# HomeAutoModule.net
KiCad netlist of a schematic drawn in EAGLE
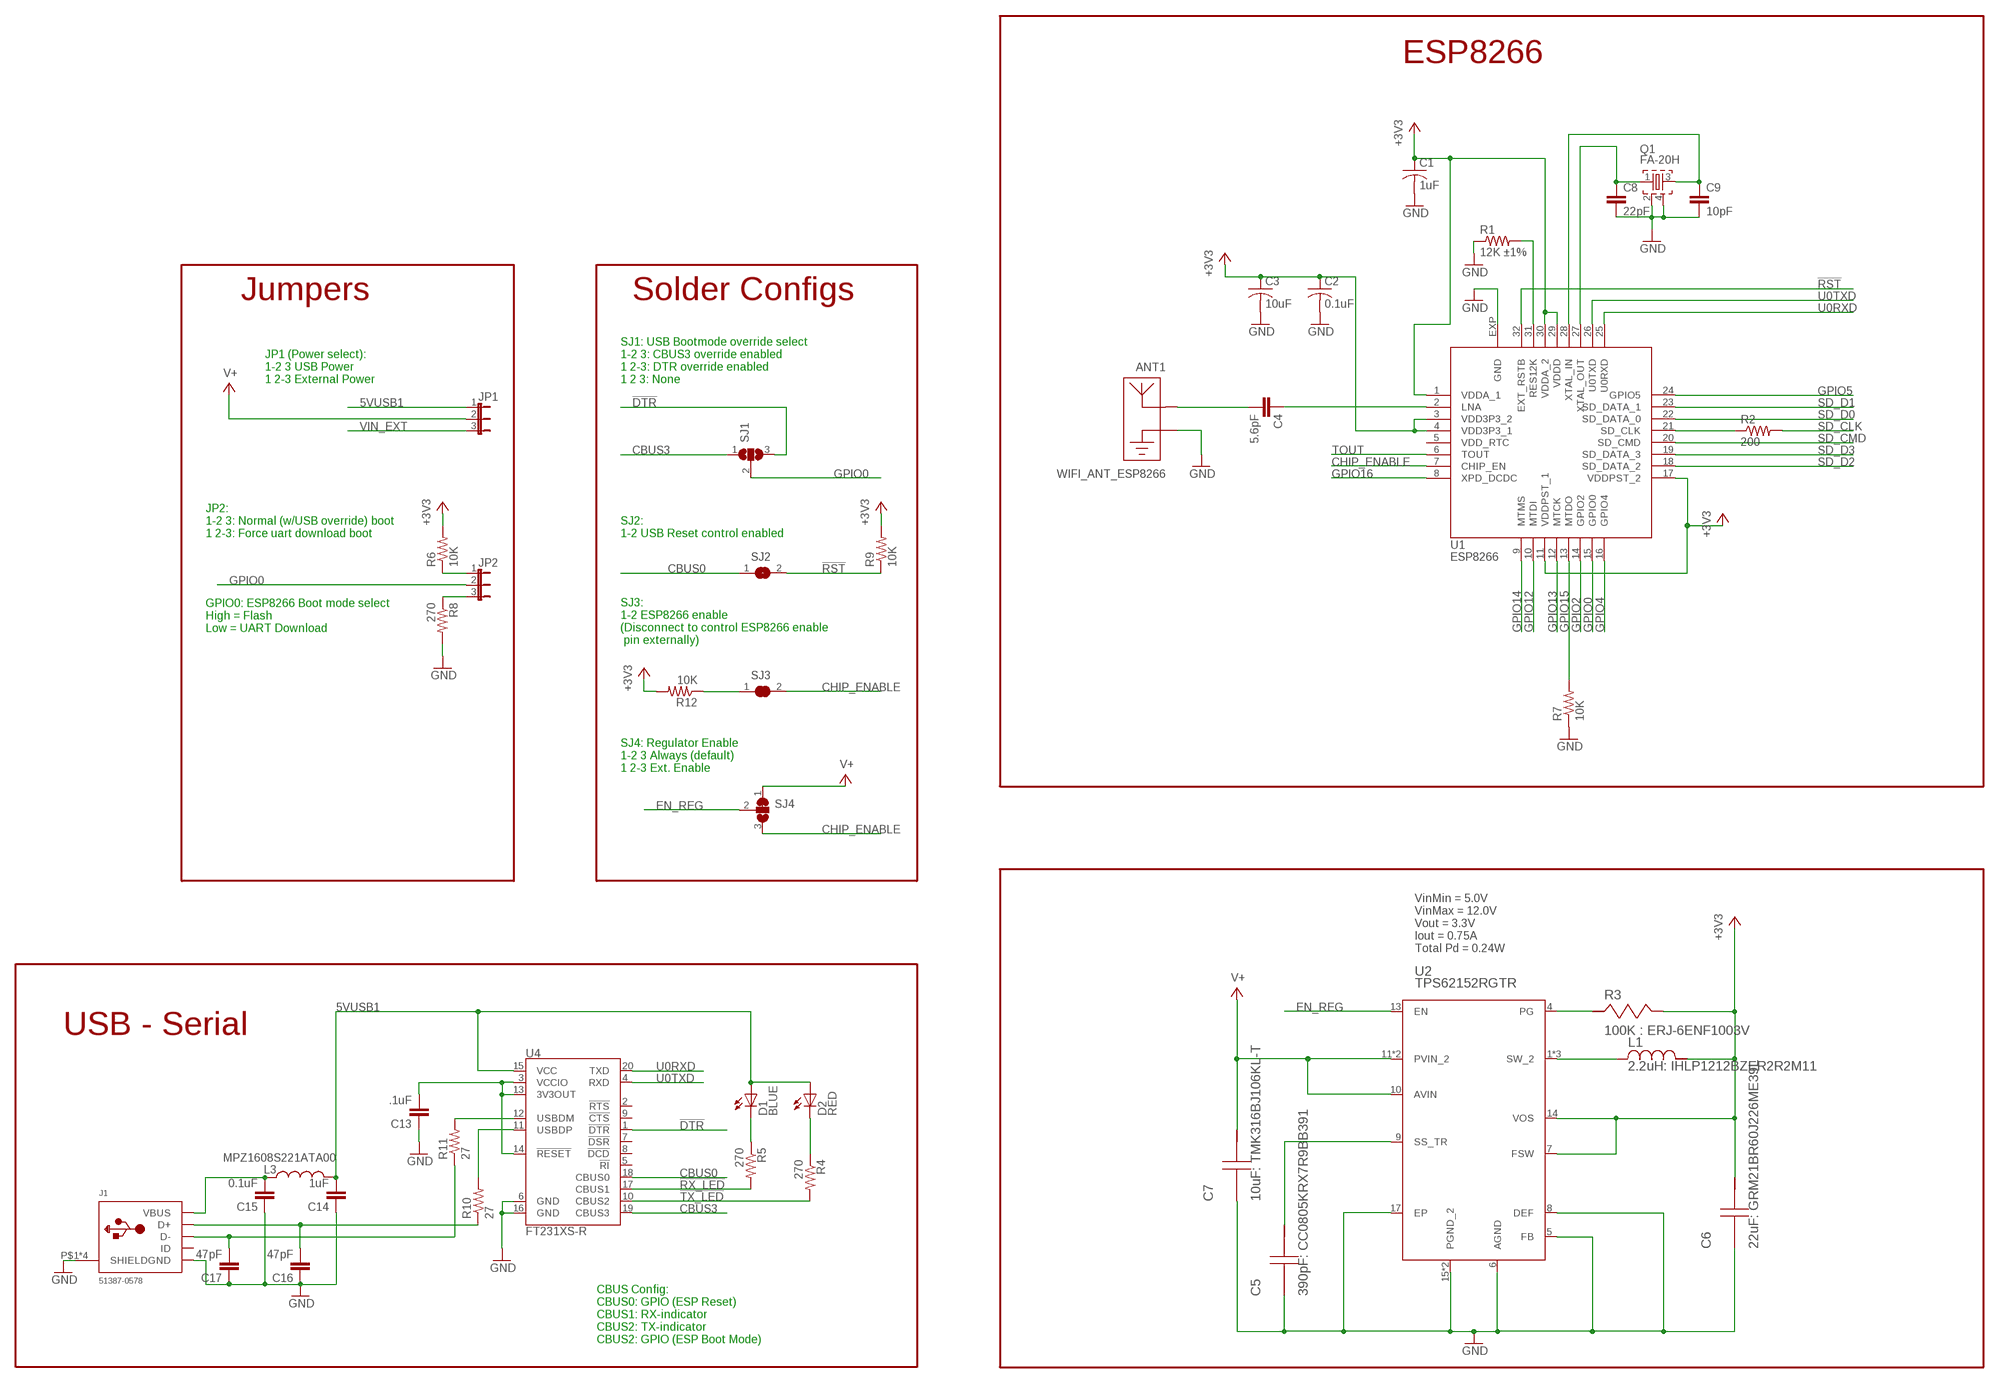
[diagram p0: schematic, sheet 1, part 1 of 2]
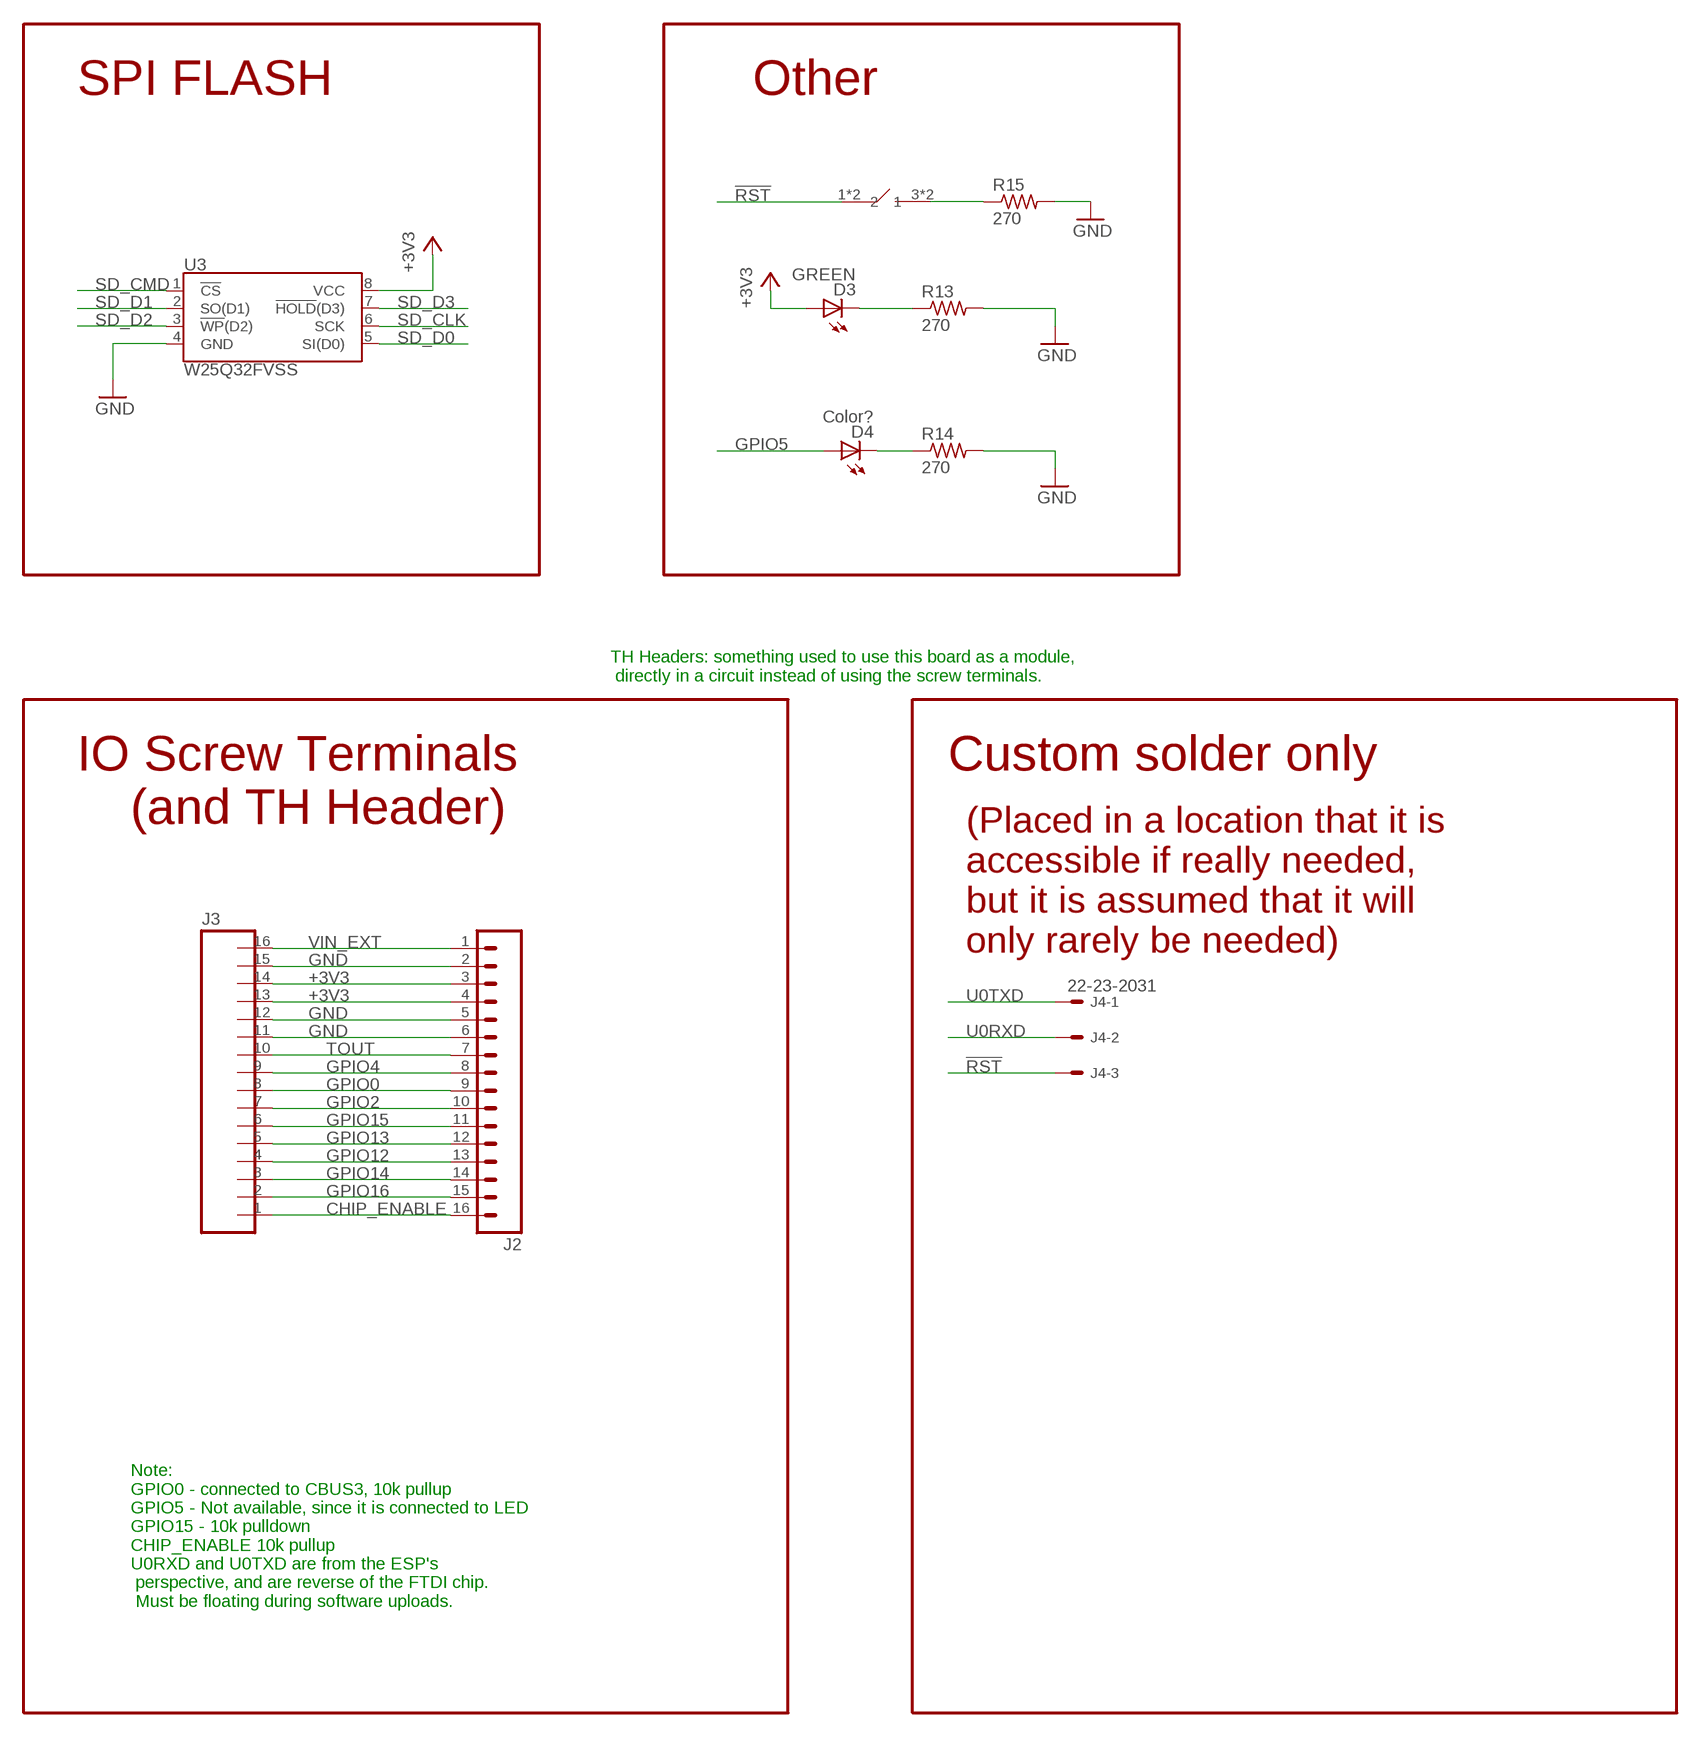
[diagram p1: schematic, sheet 1, part 2 of 2]

(export (version "E")
  (design (tool "Eeschema 10.0.6"))
  (components
    (comp (ref "ANT1")
      (value "WIFI_ANT_ESP8266")
      (footprint "eagle-import:ESP8266_ANT")
      (libsource (lib "eagle-import") (part "WIFI_ANT_ESP8266"))
    )
    (comp (ref "C1")
      (value "1uF")
      (footprint "eagle-import:C0603")
      (libsource (lib "eagle-import") (part "C-USC0603"))
    )
    (comp (ref "C2")
      (value "0.1uF")
      (footprint "eagle-import:C0603K")
      (libsource (lib "eagle-import") (part "C-USC0603K"))
    )
    (comp (ref "C3")
      (value "10uF")
      (footprint "eagle-import:C0805")
      (libsource (lib "eagle-import") (part "C-USC0805"))
    )
    (comp (ref "C4")
      (value "5.6pF")
      (footprint "eagle-import:C0603")
      (libsource (lib "eagle-import") (part "C-EUC0603"))
    )
    (comp (ref "C5")
      (value "390pF: CC0805KRX7R9BB391")
      (footprint "eagle-import:0805")
      (fields (field (name "MANUFACTURER_PART_NUMBER") "CC0805KRX7R9BB391"))
      (libsource (lib "eagle-import") (part "CC0805KRX7R9BB391"))
    )
    (comp (ref "C6")
      (value "22uF: GRM21BR60J226ME39L")
      (footprint "eagle-import:0805")
      (fields (field (name "MANUFACTURER_PART_NUMBER") "GRM21BR60J226ME39L"))
      (libsource (lib "eagle-import") (part "GRM21BR60J226ME39L"))
    )
    (comp (ref "C7")
      (value "10uF: TMK316BJ106KL-T")
      (footprint "eagle-import:1206")
      (fields (field (name "MANUFACTURER_PART_NUMBER") "TMK316BJ106KL-T"))
      (libsource (lib "eagle-import") (part "TMK316BJ106KL-T"))
    )
    (comp (ref "C8")
      (value "22pF")
      (footprint "eagle-import:C0603")
      (libsource (lib "eagle-import") (part "C-EUC0603"))
    )
    (comp (ref "C9")
      (value "10pF")
      (footprint "eagle-import:C0603")
      (libsource (lib "eagle-import") (part "C-EUC0603"))
    )
    (comp (ref "C13")
      (value ".1uF")
      (footprint "eagle-import:C0603K")
      (libsource (lib "eagle-import") (part "resistor_C-EUC0603K"))
    )
    (comp (ref "C14")
      (value "1uF")
      (footprint "eagle-import:C0603K")
      (libsource (lib "eagle-import") (part "resistor_C-EUC0603K"))
    )
    (comp (ref "C15")
      (value "0.1uF")
      (footprint "eagle-import:C0603K")
      (libsource (lib "eagle-import") (part "resistor_C-EUC0603K"))
    )
    (comp (ref "C16")
      (value "47pF")
      (footprint "eagle-import:C0603K")
      (libsource (lib "eagle-import") (part "resistor_C-EUC0603K"))
    )
    (comp (ref "C17")
      (value "47pF")
      (footprint "eagle-import:C0603K")
      (libsource (lib "eagle-import") (part "resistor_C-EUC0603K"))
    )
    (comp (ref "D1")
      (value "BLUE")
      (footprint "eagle-import:CHIPLED_0603")
      (libsource (lib "eagle-import") (part "LEDCHIPLED_0603"))
    )
    (comp (ref "D2")
      (value "RED")
      (footprint "eagle-import:CHIPLED_0603")
      (libsource (lib "eagle-import") (part "LEDCHIPLED_0603"))
    )
    (comp (ref "D3")
      (value "GREEN")
      (footprint "eagle-import:CHIPLED_0603")
      (libsource (lib "eagle-import") (part "LEDCHIPLED_0603"))
    )
    (comp (ref "D4")
      (value "Color?")
      (footprint "eagle-import:CHIPLED_0603")
      (libsource (lib "eagle-import") (part "LEDCHIPLED_0603"))
    )
    (comp (ref "J1")
      (value "51387-0578")
      (footprint "eagle-import:USB-MINIB-0513870578")
      (libsource (lib "eagle-import") (part "USB"))
    )
    (comp (ref "J2")
      (value "M161X16_NO_SILK")
      (footprint "eagle-import:1X16_NO_SILK")
      (libsource (lib "eagle-import") (part "M161X16_NO_SILK"))
    )
    (comp (ref "J3")
      (value "PTSA_250_16")
      (footprint "eagle-import:PTSA_250_16_F")
      (libsource (lib "eagle-import") (part "PTSA_250_16"))
    )
    (comp (ref "J4")
      (value "22-23-2031")
      (footprint "eagle-import:22-23-2031")
      (fields (field (name "MF") "MOLEX"))
      (libsource (lib "eagle-import") (part "22-23-2031"))
    )
    (comp (ref "JP1")
      (value "JP2E")
      (footprint "eagle-import:JP2")
      (libsource (lib "eagle-import") (part "JP2E"))
    )
    (comp (ref "JP2")
      (value "JP2E")
      (footprint "eagle-import:JP2")
      (libsource (lib "eagle-import") (part "JP2E"))
    )
    (comp (ref "L1")
      (value "2.2uH: IHLP1212BZER2R2M11")
      (footprint "eagle-import:IHLP-1212BZ")
      (fields
        (field (name "MANUFACTURER") "Vishay")
        (field (name "MANUFACTURER_PART_NUMBER") "IHLP1212BZER2R2M11")
      )
      (libsource (lib "eagle-import") (part "IHLP1212BZER2R2M11"))
    )
    (comp (ref "L3")
      (value "MPZ1608S221ATA00")
      (footprint "eagle-import:0603")
      (libsource (lib "eagle-import") (part "INDUCTOR0603"))
    )
    (comp (ref "Q1")
      (value "FA-20H")
      (footprint "eagle-import:FA-20H")
      (libsource (lib "eagle-import") (part "FA-20H"))
    )
    (comp (ref "R1")
      (value "12K ±1%")
      (footprint "eagle-import:R0603")
      (libsource (lib "eagle-import") (part "R-US_R0603"))
    )
    (comp (ref "R2")
      (value "200")
      (footprint "eagle-import:R0603")
      (libsource (lib "eagle-import") (part "R-US_R0603"))
    )
    (comp (ref "R3")
      (value "100K : ERJ-6ENF1003V")
      (footprint "eagle-import:0805")
      (fields
        (field (name "MANUFACTURER_PART_NUMBER") "ERJ-6ENF1003V")
        (field (name "POWER") "0.125")
        (field (name "TOLERANCE") "1.0")
      )
      (libsource (lib "eagle-import") (part "ERJ-6ENF1003V"))
    )
    (comp (ref "R4")
      (value "270")
      (footprint "eagle-import:R0603")
      (libsource (lib "eagle-import") (part "resistor_R-US_R0603"))
    )
    (comp (ref "R5")
      (value "270")
      (footprint "eagle-import:R0603")
      (libsource (lib "eagle-import") (part "resistor_R-US_R0603"))
    )
    (comp (ref "R6")
      (value "10K")
      (footprint "eagle-import:R0603")
      (libsource (lib "eagle-import") (part "R-US_R0603"))
    )
    (comp (ref "R7")
      (value "10K")
      (footprint "eagle-import:R0603")
      (libsource (lib "eagle-import") (part "R-US_R0603"))
    )
    (comp (ref "R8")
      (value "270")
      (footprint "eagle-import:R0603")
      (libsource (lib "eagle-import") (part "resistor_R-US_R0603"))
    )
    (comp (ref "R9")
      (value "10K")
      (footprint "eagle-import:R0603")
      (libsource (lib "eagle-import") (part "R-US_R0603"))
    )
    (comp (ref "R10")
      (value "27")
      (footprint "eagle-import:R0603")
      (libsource (lib "eagle-import") (part "resistor_R-US_R0603"))
    )
    (comp (ref "R11")
      (value "27")
      (footprint "eagle-import:R0603")
      (libsource (lib "eagle-import") (part "resistor_R-US_R0603"))
    )
    (comp (ref "R12")
      (value "10K")
      (footprint "eagle-import:R0603")
      (libsource (lib "eagle-import") (part "R-US_R0603"))
    )
    (comp (ref "R13")
      (value "270")
      (footprint "eagle-import:R0603")
      (libsource (lib "eagle-import") (part "resistor_R-US_R0603"))
    )
    (comp (ref "R14")
      (value "270")
      (footprint "eagle-import:R0603")
      (libsource (lib "eagle-import") (part "resistor_R-US_R0603"))
    )
    (comp (ref "R15")
      (value "270")
      (footprint "eagle-import:R0603")
      (libsource (lib "eagle-import") (part "resistor_R-US_R0603"))
    )
    (comp (ref "SJ1")
      (value "SJ2W")
      (footprint "eagle-import:SJ_2")
      (libsource (lib "eagle-import") (part "SJ2W"))
    )
    (comp (ref "SJ2") (value "SJ") (footprint "eagle-import:SJ") (libsource (lib "eagle-import") (part "SJ")))
    (comp (ref "SJ3")
      (value "SJ_C")
      (footprint "eagle-import:SJ_C")
      (libsource (lib "eagle-import") (part "SJ_C"))
    )
    (comp (ref "SJ4")
      (value "SJ2_C")
      (footprint "eagle-import:SJ_2_C")
      (libsource (lib "eagle-import") (part "SJ2_C"))
    )
    (comp (ref "SW1")
      (value "PTS645SM43SMTR92DEFAULT")
      (footprint "eagle-import:PTS645SM43SMTR92")
      (libsource (lib "eagle-import") (part "PTS645SM43SMTR92DEFAULT"))
    )
    (comp (ref "U1")
      (value "ESP8266")
      (footprint "eagle-import:HVQFN32")
      (libsource (lib "eagle-import") (part "ESP8266"))
    )
    (comp (ref "U2")
      (value "TPS62152RGTR")
      (footprint "eagle-import:S-PVQFN-N16")
      (fields (field (name "MANUFACTURER_PART_NUMBER") "TPS62131RGTR"))
      (libsource (lib "eagle-import") (part "TPS62152RGTR"))
    )
    (comp (ref "U3")
      (value "W25Q32FVSS")
      (footprint "eagle-import:SOIC-8")
      (libsource (lib "eagle-import") (part "W25Q32FVSS"))
    )
    (comp (ref "U4")
      (value "FT231XS-R")
      (footprint "eagle-import:SSOP20_L")
      (libsource (lib "eagle-import") (part "FT231XS"))
    )
  )
  (nets
    (net (code "1") (name "+3V3") (class "Default")
      (node (ref "C1") (pin "1") (pinfunction "1_1") (pintype "passive"))
      (node (ref "C2") (pin "1") (pinfunction "1_1") (pintype "passive"))
      (node (ref "C3") (pin "1") (pinfunction "1_1") (pintype "passive"))
      (node (ref "C6") (pin "1") (pinfunction "1_1") (pintype "passive"))
      (node (ref "D3") (pin "A") (pinfunction "A_A") (pintype "passive"))
      (node (ref "J2") (pin "3") (pinfunction "3_3") (pintype "passive"))
      (node (ref "J2") (pin "4") (pinfunction "4_4") (pintype "passive"))
      (node (ref "J3") (pin "13") (pinfunction "13_13") (pintype "bidirectional"))
      (node (ref "J3") (pin "14") (pinfunction "14_14") (pintype "bidirectional"))
      (node (ref "L1") (pin "2") (pinfunction "2_2") (pintype "passive"))
      (node (ref "R12") (pin "2") (pinfunction "2_2") (pintype "passive"))
      (node (ref "R3") (pin "1") (pinfunction "1_1") (pintype "passive"))
      (node (ref "R6") (pin "2") (pinfunction "2_2") (pintype "passive"))
      (node (ref "R9") (pin "2") (pinfunction "2_2") (pintype "passive"))
      (node (ref "U1") (pin "1") (pinfunction "VDDA_1_1") (pintype "bidirectional"))
      (node (ref "U1") (pin "11") (pinfunction "VDDPST_1_11") (pintype "bidirectional"))
      (node (ref "U1") (pin "17") (pinfunction "VDDPST_2_17") (pintype "bidirectional"))
      (node (ref "U1") (pin "29") (pinfunction "VDDD_29") (pintype "bidirectional"))
      (node (ref "U1") (pin "3") (pinfunction "VDD3P3_2_3") (pintype "bidirectional"))
      (node (ref "U1") (pin "30") (pinfunction "VDDA_2_30") (pintype "bidirectional"))
      (node (ref "U1") (pin "4") (pinfunction "VDD3P3_1_4") (pintype "bidirectional"))
      (node (ref "U2") (pin "14") (pinfunction "VOS_14") (pintype "passive"))
      (node (ref "U2") (pin "7") (pinfunction "FSW_7") (pintype "passive"))
      (node (ref "U3") (pin "8") (pinfunction "VCC_8") (pintype "bidirectional"))
    )
    (net (code "2") (name "/5VUSB1") (class "Default")
      (node (ref "C14") (pin "2") (pinfunction "2_2") (pintype "passive"))
      (node (ref "D1") (pin "A") (pinfunction "A_A") (pintype "passive"))
      (node (ref "D2") (pin "A") (pinfunction "A_A") (pintype "passive"))
      (node (ref "JP1") (pin "1") (pinfunction "1_1") (pintype "passive"))
      (node (ref "L3") (pin "2") (pinfunction "2_2") (pintype "passive"))
      (node (ref "U4") (pin "15") (pinfunction "VCC_15") (pintype "bidirectional"))
    )
    (net (code "3") (name "/CBUS0") (class "Default")
      (node (ref "SJ2") (pin "1") (pinfunction "1_1") (pintype "passive"))
      (node (ref "U4") (pin "18") (pinfunction "CBUS0_18") (pintype "bidirectional"))
    )
    (net (code "4") (name "/CBUS3") (class "Default")
      (node (ref "SJ1") (pin "1") (pinfunction "1_1") (pintype "passive"))
      (node (ref "U4") (pin "19") (pinfunction "CBUS3_19") (pintype "bidirectional"))
    )
    (net (code "5") (name "/CHIP_ENABLE") (class "Default")
      (node (ref "J2") (pin "16") (pinfunction "16_16") (pintype "passive"))
      (node (ref "J3") (pin "1") (pinfunction "1_1") (pintype "bidirectional"))
      (node (ref "SJ3") (pin "2") (pinfunction "2_2") (pintype "passive"))
      (node (ref "SJ4") (pin "3") (pinfunction "3_3") (pintype "passive"))
      (node (ref "U1") (pin "7") (pinfunction "CHIP_EN_7") (pintype "bidirectional"))
    )
    (net (code "6") (name "/EN_REG") (class "Default")
      (node (ref "SJ4") (pin "2") (pinfunction "2_2") (pintype "passive"))
      (node (ref "U2") (pin "13") (pinfunction "EN_13") (pintype "passive"))
    )
    (net (code "7") (name "/GPIO0") (class "Default")
      (node (ref "J2") (pin "9") (pinfunction "9_9") (pintype "passive"))
      (node (ref "J3") (pin "8") (pinfunction "8_8") (pintype "bidirectional"))
      (node (ref "JP2") (pin "2") (pinfunction "2_2") (pintype "passive"))
      (node (ref "SJ1") (pin "2") (pinfunction "2_2") (pintype "passive"))
      (node (ref "U1") (pin "15") (pinfunction "GPIO0_15") (pintype "bidirectional"))
    )
    (net (code "8") (name "/GPIO2") (class "Default")
      (node (ref "J2") (pin "10") (pinfunction "10_10") (pintype "passive"))
      (node (ref "J3") (pin "7") (pinfunction "7_7") (pintype "bidirectional"))
      (node (ref "U1") (pin "14") (pinfunction "GPIO2_14") (pintype "bidirectional"))
    )
    (net (code "9") (name "/GPIO4") (class "Default")
      (node (ref "J2") (pin "8") (pinfunction "8_8") (pintype "passive"))
      (node (ref "J3") (pin "9") (pinfunction "9_9") (pintype "bidirectional"))
      (node (ref "U1") (pin "16") (pinfunction "GPIO4_16") (pintype "bidirectional"))
    )
    (net (code "10") (name "/GPIO5") (class "Default")
      (node (ref "D4") (pin "A") (pinfunction "A_A") (pintype "passive"))
      (node (ref "U1") (pin "24") (pinfunction "GPIO5_24") (pintype "bidirectional"))
    )
    (net (code "11") (name "/GPIO12") (class "Default")
      (node (ref "J2") (pin "13") (pinfunction "13_13") (pintype "passive"))
      (node (ref "J3") (pin "4") (pinfunction "4_4") (pintype "bidirectional"))
      (node (ref "U1") (pin "10") (pinfunction "MTDI_10") (pintype "bidirectional"))
    )
    (net (code "12") (name "/GPIO13") (class "Default")
      (node (ref "J2") (pin "12") (pinfunction "12_12") (pintype "passive"))
      (node (ref "J3") (pin "5") (pinfunction "5_5") (pintype "bidirectional"))
      (node (ref "U1") (pin "12") (pinfunction "MTCK_12") (pintype "bidirectional"))
    )
    (net (code "13") (name "/GPIO14") (class "Default")
      (node (ref "J2") (pin "14") (pinfunction "14_14") (pintype "passive"))
      (node (ref "J3") (pin "3") (pinfunction "3_3") (pintype "bidirectional"))
      (node (ref "U1") (pin "9") (pinfunction "MTMS_9") (pintype "bidirectional"))
    )
    (net (code "14") (name "/GPIO15") (class "Default")
      (node (ref "J2") (pin "11") (pinfunction "11_11") (pintype "passive"))
      (node (ref "J3") (pin "6") (pinfunction "6_6") (pintype "bidirectional"))
      (node (ref "R7") (pin "2") (pinfunction "2_2") (pintype "passive"))
      (node (ref "U1") (pin "13") (pinfunction "MTDO_13") (pintype "bidirectional"))
    )
    (net (code "15") (name "/GPIO16") (class "Default")
      (node (ref "J2") (pin "15") (pinfunction "15_15") (pintype "passive"))
      (node (ref "J3") (pin "2") (pinfunction "2_2") (pintype "bidirectional"))
      (node (ref "U1") (pin "8") (pinfunction "XPD_DCDC_8") (pintype "bidirectional"))
    )
    (net (code "16") (name "/SD_CLK") (class "Default")
      (node (ref "R2") (pin "2") (pinfunction "2_2") (pintype "passive"))
      (node (ref "U3") (pin "6") (pinfunction "SCK_6") (pintype "bidirectional"))
    )
    (net (code "17") (name "/SD_CMD") (class "Default")
      (node (ref "U1") (pin "20") (pinfunction "SD_CMD_20") (pintype "bidirectional"))
      (node (ref "U3") (pin "1") (pinfunction "~{CS}_1") (pintype "bidirectional"))
    )
    (net (code "18") (name "/SD_D0") (class "Default")
      (node (ref "U1") (pin "22") (pinfunction "SD_DATA_0_22") (pintype "bidirectional"))
      (node (ref "U3") (pin "5") (pinfunction "SI(D0)_5") (pintype "bidirectional"))
    )
    (net (code "19") (name "/SD_D1") (class "Default")
      (node (ref "U1") (pin "23") (pinfunction "SD_DATA_1_23") (pintype "bidirectional"))
      (node (ref "U3") (pin "2") (pinfunction "SO(D1)_2") (pintype "bidirectional"))
    )
    (net (code "20") (name "/SD_D2") (class "Default")
      (node (ref "U1") (pin "18") (pinfunction "SD_DATA_2_18") (pintype "bidirectional"))
      (node (ref "U3") (pin "3") (pinfunction "~{WP}(D2)_3") (pintype "bidirectional"))
    )
    (net (code "21") (name "/SD_D3") (class "Default")
      (node (ref "U1") (pin "19") (pinfunction "SD_DATA_3_19") (pintype "bidirectional"))
      (node (ref "U3") (pin "7") (pinfunction "~{HOLD}(D3)_7") (pintype "bidirectional"))
    )
    (net (code "22") (name "/TOUT") (class "Default")
      (node (ref "J2") (pin "7") (pinfunction "7_7") (pintype "passive"))
      (node (ref "J3") (pin "10") (pinfunction "10_10") (pintype "bidirectional"))
      (node (ref "U1") (pin "6") (pinfunction "TOUT_6") (pintype "bidirectional"))
    )
    (net (code "23") (name "/U0RXD") (class "Default")
      (node (ref "J4") (pin "2") (pinfunction "S_2") (pintype "passive"))
      (node (ref "U1") (pin "25") (pinfunction "U0RXD_25") (pintype "bidirectional"))
      (node (ref "U4") (pin "20") (pinfunction "TXD_20") (pintype "bidirectional"))
    )
    (net (code "24") (name "/U0TXD") (class "Default")
      (node (ref "J4") (pin "1") (pinfunction "S_1") (pintype "passive"))
      (node (ref "U1") (pin "26") (pinfunction "U0TXD_26") (pintype "bidirectional"))
      (node (ref "U4") (pin "4") (pinfunction "RXD_4") (pintype "bidirectional"))
    )
    (net (code "25") (name "/VIN_EXT") (class "Default")
      (node (ref "J2") (pin "1") (pinfunction "1_1") (pintype "passive"))
      (node (ref "J3") (pin "16") (pinfunction "16_16") (pintype "bidirectional"))
      (node (ref "JP1") (pin "3") (pinfunction "3_3") (pintype "passive"))
    )
    (net (code "26") (name "/~{DTR}") (class "Default")
      (node (ref "SJ1") (pin "3") (pinfunction "3_3") (pintype "passive"))
      (node (ref "U4") (pin "1") (pinfunction "~{DTR}_1") (pintype "bidirectional"))
    )
    (net (code "27") (name "/~{RST}") (class "Default")
      (node (ref "J4") (pin "3") (pinfunction "S_3") (pintype "passive"))
      (node (ref "R9") (pin "1") (pinfunction "1_1") (pintype "passive"))
      (node (ref "SJ2") (pin "2") (pinfunction "2_2") (pintype "passive"))
      (node (ref "SW1") (pin "1") (pinfunction "1_1") (pintype "bidirectional"))
      (node (ref "SW1") (pin "2") (pinfunction "1_2") (pintype "bidirectional"))
      (node (ref "U1") (pin "32") (pinfunction "EXT_RSTB_32") (pintype "bidirectional"))
    )
    (net (code "28") (name "/~{RX_LED}") (class "Default")
      (node (ref "R5") (pin "2") (pinfunction "2_2") (pintype "passive"))
      (node (ref "U4") (pin "17") (pinfunction "CBUS1_17") (pintype "bidirectional"))
    )
    (net (code "29") (name "/~{TX_LED}") (class "Default")
      (node (ref "R4") (pin "2") (pinfunction "2_2") (pintype "passive"))
      (node (ref "U4") (pin "10") (pinfunction "CBUS2_10") (pintype "bidirectional"))
    )
    (net (code "30") (name "GND") (class "Default")
      (node (ref "ANT1") (pin "GND") (pinfunction "GND_GND") (pintype "input"))
      (node (ref "C1") (pin "2") (pinfunction "2_2") (pintype "passive"))
      (node (ref "C13") (pin "1") (pinfunction "1_1") (pintype "passive"))
      (node (ref "C14") (pin "1") (pinfunction "1_1") (pintype "passive"))
      (node (ref "C15") (pin "1") (pinfunction "1_1") (pintype "passive"))
      (node (ref "C16") (pin "1") (pinfunction "1_1") (pintype "passive"))
      (node (ref "C17") (pin "1") (pinfunction "1_1") (pintype "passive"))
      (node (ref "C2") (pin "2") (pinfunction "2_2") (pintype "passive"))
      (node (ref "C3") (pin "2") (pinfunction "2_2") (pintype "passive"))
      (node (ref "C5") (pin "2") (pinfunction "2_2") (pintype "passive"))
      (node (ref "C6") (pin "2") (pinfunction "2_2") (pintype "passive"))
      (node (ref "C7") (pin "2") (pinfunction "2_2") (pintype "passive"))
      (node (ref "C8") (pin "2") (pinfunction "2_2") (pintype "passive"))
      (node (ref "C9") (pin "2") (pinfunction "2_2") (pintype "passive"))
      (node (ref "J1") (pin "GND") (pinfunction "GND_GND") (pintype "power_in"))
      (node (ref "J1") (pin "P$1") (pinfunction "SHIELD_P$1") (pintype "bidirectional"))
      (node (ref "J1") (pin "P$2") (pinfunction "SHIELD_P$2") (pintype "bidirectional"))
      (node (ref "J1") (pin "P$3") (pinfunction "SHIELD_P$3") (pintype "bidirectional"))
      (node (ref "J1") (pin "P$4") (pinfunction "SHIELD_P$4") (pintype "bidirectional"))
      (node (ref "J2") (pin "2") (pinfunction "2_2") (pintype "passive"))
      (node (ref "J2") (pin "5") (pinfunction "5_5") (pintype "passive"))
      (node (ref "J2") (pin "6") (pinfunction "6_6") (pintype "passive"))
      (node (ref "J3") (pin "11") (pinfunction "11_11") (pintype "bidirectional"))
      (node (ref "J3") (pin "12") (pinfunction "12_12") (pintype "bidirectional"))
      (node (ref "J3") (pin "15") (pinfunction "15_15") (pintype "bidirectional"))
      (node (ref "Q1") (pin "2") (pinfunction "2_2") (pintype "passive"))
      (node (ref "Q1") (pin "4") (pinfunction "4_4") (pintype "passive"))
      (node (ref "R1") (pin "1") (pinfunction "1_1") (pintype "passive"))
      (node (ref "R13") (pin "2") (pinfunction "2_2") (pintype "passive"))
      (node (ref "R14") (pin "2") (pinfunction "2_2") (pintype "passive"))
      (node (ref "R15") (pin "2") (pinfunction "2_2") (pintype "passive"))
      (node (ref "R7") (pin "1") (pinfunction "1_1") (pintype "passive"))
      (node (ref "R8") (pin "2") (pinfunction "2_2") (pintype "passive"))
      (node (ref "U1") (pin "EXP") (pinfunction "GND_EXP") (pintype "bidirectional"))
      (node (ref "U2") (pin "15") (pinfunction "PGND_2_15") (pintype "passive"))
      (node (ref "U2") (pin "16") (pinfunction "PGND_2_16") (pintype "passive"))
      (node (ref "U2") (pin "17") (pinfunction "EP_17") (pintype "passive"))
      (node (ref "U2") (pin "5") (pinfunction "FB_5") (pintype "passive"))
      (node (ref "U2") (pin "6") (pinfunction "AGND_6") (pintype "passive"))
      (node (ref "U2") (pin "8") (pinfunction "DEF_8") (pintype "passive"))
      (node (ref "U3") (pin "4") (pinfunction "GND_4") (pintype "bidirectional"))
      (node (ref "U4") (pin "16") (pinfunction "GND_16") (pintype "bidirectional"))
      (node (ref "U4") (pin "6") (pinfunction "GND_6") (pintype "bidirectional"))
    )
    (net (code "31") (name "Net-(ANT1-PadANT)") (class "Default")
      (node (ref "ANT1") (pin "ANT") (pinfunction "ANT_ANT") (pintype "input"))
      (node (ref "C4") (pin "2") (pinfunction "2_2") (pintype "passive"))
    )
    (net (code "32") (name "Net-(C15-Pad2)") (class "Default")
      (node (ref "C15") (pin "2") (pinfunction "2_2") (pintype "passive"))
      (node (ref "J1") (pin "VBUS") (pinfunction "VBUS_VBUS") (pintype "power_in"))
      (node (ref "L3") (pin "1") (pinfunction "1_1") (pintype "passive"))
    )
    (net (code "33") (name "Net-(C16-Pad2)") (class "Default")
      (node (ref "C16") (pin "2") (pinfunction "2_2") (pintype "passive"))
      (node (ref "J1") (pin "D+") (pinfunction "D+_D+") (pintype "bidirectional"))
      (node (ref "R10") (pin "1") (pinfunction "1_1") (pintype "passive"))
    )
    (net (code "34") (name "Net-(C17-Pad2)") (class "Default")
      (node (ref "C17") (pin "2") (pinfunction "2_2") (pintype "passive"))
      (node (ref "J1") (pin "D-") (pinfunction "D-_D-") (pintype "bidirectional"))
      (node (ref "R11") (pin "1") (pinfunction "1_1") (pintype "passive"))
    )
    (net (code "35") (name "Net-(D1-PadC)") (class "Default")
      (node (ref "D1") (pin "C") (pinfunction "C_C") (pintype "passive"))
      (node (ref "R5") (pin "1") (pinfunction "1_1") (pintype "passive"))
    )
    (net (code "36") (name "Net-(D2-PadC)") (class "Default")
      (node (ref "D2") (pin "C") (pinfunction "C_C") (pintype "passive"))
      (node (ref "R4") (pin "1") (pinfunction "1_1") (pintype "passive"))
    )
    (net (code "37") (name "Net-(D3-PadC)") (class "Default")
      (node (ref "D3") (pin "C") (pinfunction "C_C") (pintype "passive"))
      (node (ref "R13") (pin "1") (pinfunction "1_1") (pintype "passive"))
    )
    (net (code "38") (name "Net-(D4-PadC)") (class "Default")
      (node (ref "D4") (pin "C") (pinfunction "C_C") (pintype "passive"))
      (node (ref "R14") (pin "1") (pinfunction "1_1") (pintype "passive"))
    )
    (net (code "39") (name "Net-(JP2-Pad1)") (class "Default")
      (node (ref "JP2") (pin "1") (pinfunction "1_1") (pintype "passive"))
      (node (ref "R6") (pin "1") (pinfunction "1_1") (pintype "passive"))
    )
    (net (code "40") (name "Net-(JP2-Pad3)") (class "Default")
      (node (ref "JP2") (pin "3") (pinfunction "3_3") (pintype "passive"))
      (node (ref "R8") (pin "1") (pinfunction "1_1") (pintype "passive"))
    )
    (net (code "41") (name "Net-(L1-Pad1)") (class "Default")
      (node (ref "L1") (pin "1") (pinfunction "1_1") (pintype "passive"))
      (node (ref "U2") (pin "1") (pinfunction "SW_2_1") (pintype "passive"))
      (node (ref "U2") (pin "2") (pinfunction "SW_2_2") (pintype "passive"))
      (node (ref "U2") (pin "3") (pinfunction "SW_2_3") (pintype "passive"))
    )
    (net (code "42") (name "Net-(R12-Pad1)") (class "Default")
      (node (ref "R12") (pin "1") (pinfunction "1_1") (pintype "passive"))
      (node (ref "SJ3") (pin "1") (pinfunction "1_1") (pintype "passive"))
    )
    (net (code "43") (name "Net-(R15-Pad1)") (class "Default")
      (node (ref "R15") (pin "1") (pinfunction "1_1") (pintype "passive"))
      (node (ref "SW1") (pin "3") (pinfunction "2_3") (pintype "bidirectional"))
      (node (ref "SW1") (pin "4") (pinfunction "2_4") (pintype "bidirectional"))
    )
    (net (code "44") (name "Net-(U1-LNA)") (class "Default")
      (node (ref "C4") (pin "1") (pinfunction "1_1") (pintype "passive"))
      (node (ref "U1") (pin "2") (pinfunction "LNA_2") (pintype "bidirectional"))
    )
    (net (code "45") (name "Net-(U1-RES12K)") (class "Default")
      (node (ref "R1") (pin "2") (pinfunction "2_2") (pintype "passive"))
      (node (ref "U1") (pin "31") (pinfunction "RES12K_31") (pintype "bidirectional"))
    )
    (net (code "46") (name "Net-(U1-SD_CLK)") (class "Default")
      (node (ref "R2") (pin "1") (pinfunction "1_1") (pintype "passive"))
      (node (ref "U1") (pin "21") (pinfunction "SD_CLK_21") (pintype "bidirectional"))
    )
    (net (code "47") (name "Net-(U1-XTAL_IN)") (class "Default")
      (node (ref "C9") (pin "1") (pinfunction "1_1") (pintype "passive"))
      (node (ref "Q1") (pin "3") (pinfunction "3_3") (pintype "passive"))
      (node (ref "U1") (pin "28") (pinfunction "XTAL_IN_28") (pintype "bidirectional"))
    )
    (net (code "48") (name "Net-(U1-XTAL_OUT)") (class "Default")
      (node (ref "C8") (pin "1") (pinfunction "1_1") (pintype "passive"))
      (node (ref "Q1") (pin "1") (pinfunction "1_1") (pintype "passive"))
      (node (ref "U1") (pin "27") (pinfunction "XTAL_OUT_27") (pintype "bidirectional"))
    )
    (net (code "49") (name "Net-(U2-PG)") (class "Default")
      (node (ref "R3") (pin "2") (pinfunction "2_2") (pintype "passive"))
      (node (ref "U2") (pin "4") (pinfunction "PG_4") (pintype "passive"))
    )
    (net (code "50") (name "Net-(U2-SS_TR)") (class "Default")
      (node (ref "C5") (pin "1") (pinfunction "1_1") (pintype "passive"))
      (node (ref "U2") (pin "9") (pinfunction "SS_TR_9") (pintype "passive"))
    )
    (net (code "51") (name "Net-(U4-3V3OUT)") (class "Default")
      (node (ref "C13") (pin "2") (pinfunction "2_2") (pintype "passive"))
      (node (ref "U4") (pin "13") (pinfunction "3V3OUT_13") (pintype "bidirectional"))
      (node (ref "U4") (pin "14") (pinfunction "~{RESET}_14") (pintype "bidirectional"))
      (node (ref "U4") (pin "3") (pinfunction "VCCIO_3") (pintype "bidirectional"))
    )
    (net (code "52") (name "Net-(U4-USBDM)") (class "Default")
      (node (ref "R11") (pin "2") (pinfunction "2_2") (pintype "passive"))
      (node (ref "U4") (pin "12") (pinfunction "USBDM_12") (pintype "bidirectional"))
    )
    (net (code "53") (name "Net-(U4-USBDP)") (class "Default")
      (node (ref "R10") (pin "2") (pinfunction "2_2") (pintype "passive"))
      (node (ref "U4") (pin "11") (pinfunction "USBDP_11") (pintype "bidirectional"))
    )
    (net (code "54") (name "V+") (class "Default")
      (node (ref "C7") (pin "1") (pinfunction "1_1") (pintype "passive"))
      (node (ref "JP1") (pin "2") (pinfunction "2_2") (pintype "passive"))
      (node (ref "SJ4") (pin "1") (pinfunction "1_1") (pintype "passive"))
      (node (ref "U2") (pin "10") (pinfunction "AVIN_10") (pintype "passive"))
      (node (ref "U2") (pin "11") (pinfunction "PVIN_2_11") (pintype "passive"))
      (node (ref "U2") (pin "12") (pinfunction "PVIN_2_12") (pintype "passive"))
    )
    (net (code "55") (name "unconnected-(J1-PadID)") (class "Default")
      (node (ref "J1") (pin "ID") (pinfunction "ID_ID") (pintype "bidirectional"))
    )
    (net (code "56") (name "unconnected-(U1-VDD_RTC-Pad5)") (class "Default")
      (node (ref "U1") (pin "5") (pinfunction "VDD_RTC_5") (pintype "bidirectional"))
    )
    (net (code "57") (name "unconnected-(U4-~{CTS}-Pad9)") (class "Default")
      (node (ref "U4") (pin "9") (pinfunction "~{CTS}_9") (pintype "bidirectional"))
    )
    (net (code "58") (name "unconnected-(U4-~{DCD}-Pad8)") (class "Default")
      (node (ref "U4") (pin "8") (pinfunction "~{DCD}_8") (pintype "bidirectional"))
    )
    (net (code "59") (name "unconnected-(U4-~{DSR}-Pad7)") (class "Default")
      (node (ref "U4") (pin "7") (pinfunction "~{DSR}_7") (pintype "bidirectional"))
    )
    (net (code "60") (name "unconnected-(U4-~{RI}-Pad5)") (class "Default")
      (node (ref "U4") (pin "5") (pinfunction "~{RI}_5") (pintype "bidirectional"))
    )
    (net (code "61") (name "unconnected-(U4-~{RTS}-Pad2)") (class "Default")
      (node (ref "U4") (pin "2") (pinfunction "~{RTS}_2") (pintype "bidirectional"))
    )
  )
)
